# Connectors.net
KiCad netlist of a schematic drawn in Altium Designer
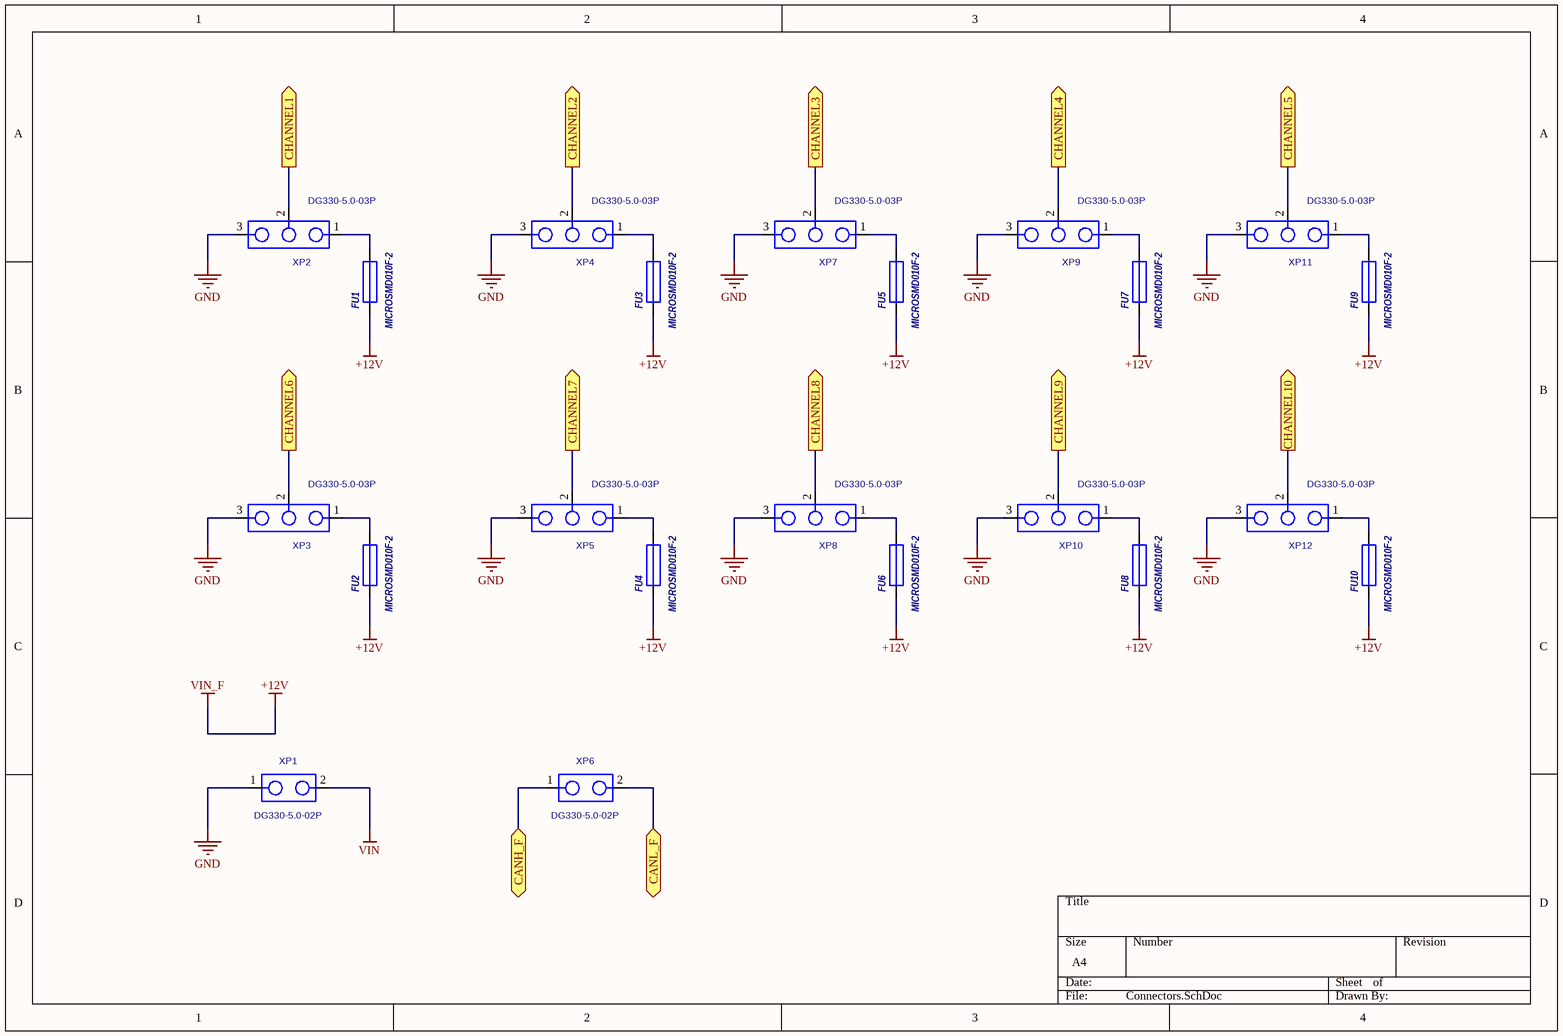
[diagram p0: Connectors.SchDoc]

(export (version "E")
  (design (tool "Eeschema 10.0.6"))
  (components
    (comp (ref "FU1")
      (value "MICROSMD010F-2")
      (footprint "RC1210")
      (description "MICROSMD")
      (libsource (lib "gprs_modem_2") (part "MICROSMD"))
    )
    (comp (ref "FU2")
      (value "MICROSMD010F-2")
      (footprint "RC1210")
      (description "MICROSMD")
      (libsource (lib "gprs_modem_2") (part "MICROSMD"))
    )
    (comp (ref "FU3")
      (value "MICROSMD010F-2")
      (footprint "RC1210")
      (description "MICROSMD")
      (libsource (lib "gprs_modem_2") (part "MICROSMD"))
    )
    (comp (ref "FU4")
      (value "MICROSMD010F-2")
      (footprint "RC1210")
      (description "MICROSMD")
      (libsource (lib "gprs_modem_2") (part "MICROSMD"))
    )
    (comp (ref "FU5")
      (value "MICROSMD010F-2")
      (footprint "RC1210")
      (description "MICROSMD")
      (libsource (lib "gprs_modem_2") (part "MICROSMD"))
    )
    (comp (ref "FU6")
      (value "MICROSMD010F-2")
      (footprint "RC1210")
      (description "MICROSMD")
      (libsource (lib "gprs_modem_2") (part "MICROSMD"))
    )
    (comp (ref "FU7")
      (value "MICROSMD010F-2")
      (footprint "RC1210")
      (description "MICROSMD")
      (libsource (lib "gprs_modem_2") (part "MICROSMD"))
    )
    (comp (ref "FU8")
      (value "MICROSMD010F-2")
      (footprint "RC1210")
      (description "MICROSMD")
      (libsource (lib "gprs_modem_2") (part "MICROSMD"))
    )
    (comp (ref "FU9")
      (value "MICROSMD010F-2")
      (footprint "RC1210")
      (description "MICROSMD")
      (libsource (lib "gprs_modem_2") (part "MICROSMD"))
    )
    (comp (ref "FU10")
      (value "MICROSMD010F-2")
      (footprint "RC1210")
      (description "MICROSMD")
      (libsource (lib "gprs_modem_2") (part "MICROSMD"))
    )
    (comp (ref "XP1")
      (value "DG330-5.0-02P")
      (footprint "330-021")
      (libsource (lib "shlagbaum") (part "DG330-5.0-02P"))
    )
    (comp (ref "XP2")
      (value "DG330-5.0-03P")
      (footprint "DG330-5.0-03P")
      (libsource (lib "shlagbaum") (part "DG330-5.0-03P"))
    )
    (comp (ref "XP3")
      (value "DG330-5.0-03P")
      (footprint "DG330-5.0-03P")
      (libsource (lib "shlagbaum") (part "DG330-5.0-03P"))
    )
    (comp (ref "XP4")
      (value "DG330-5.0-03P")
      (footprint "DG330-5.0-03P")
      (libsource (lib "shlagbaum") (part "DG330-5.0-03P"))
    )
    (comp (ref "XP5")
      (value "DG330-5.0-03P")
      (footprint "DG330-5.0-03P")
      (libsource (lib "shlagbaum") (part "DG330-5.0-03P"))
    )
    (comp (ref "XP6")
      (value "DG330-5.0-02P")
      (footprint "330-021")
      (libsource (lib "shlagbaum") (part "DG330-5.0-02P"))
    )
    (comp (ref "XP7")
      (value "DG330-5.0-03P")
      (footprint "DG330-5.0-03P")
      (libsource (lib "shlagbaum") (part "DG330-5.0-03P"))
    )
    (comp (ref "XP8")
      (value "DG330-5.0-03P")
      (footprint "DG330-5.0-03P")
      (libsource (lib "shlagbaum") (part "DG330-5.0-03P"))
    )
    (comp (ref "XP9")
      (value "DG330-5.0-03P")
      (footprint "DG330-5.0-03P")
      (libsource (lib "shlagbaum") (part "DG330-5.0-03P"))
    )
    (comp (ref "XP10")
      (value "DG330-5.0-03P")
      (footprint "DG330-5.0-03P")
      (libsource (lib "shlagbaum") (part "DG330-5.0-03P"))
    )
    (comp (ref "XP11")
      (value "DG330-5.0-03P")
      (footprint "DG330-5.0-03P")
      (libsource (lib "shlagbaum") (part "DG330-5.0-03P"))
    )
    (comp (ref "XP12")
      (value "DG330-5.0-03P")
      (footprint "DG330-5.0-03P")
      (libsource (lib "shlagbaum") (part "DG330-5.0-03P"))
    )
  )
  (nets
    (net (code "1") (name "+12V") (class "Default")
      (node (ref "FU1") (pin "1") (pintype "passive"))
      (node (ref "FU10") (pin "1") (pintype "passive"))
      (node (ref "FU2") (pin "1") (pintype "passive"))
      (node (ref "FU3") (pin "1") (pintype "passive"))
      (node (ref "FU4") (pin "1") (pintype "passive"))
      (node (ref "FU5") (pin "1") (pintype "passive"))
      (node (ref "FU6") (pin "1") (pintype "passive"))
      (node (ref "FU7") (pin "1") (pintype "passive"))
      (node (ref "FU8") (pin "1") (pintype "passive"))
      (node (ref "FU9") (pin "1") (pintype "passive"))
    )
    (net (code "2") (name "/CANH_F") (class "Default") (node (ref "XP6") (pin "1") (pintype "passive")))
    (net (code "3") (name "/CANL_F") (class "Default") (node (ref "XP6") (pin "2") (pintype "passive")))
    (net (code "4") (name "/CHANNEL1") (class "Default") (node (ref "XP2") (pin "2") (pintype "passive")))
    (net (code "5") (name "/CHANNEL2") (class "Default") (node (ref "XP4") (pin "2") (pintype "passive")))
    (net (code "6") (name "/CHANNEL3") (class "Default") (node (ref "XP7") (pin "2") (pintype "passive")))
    (net (code "7") (name "/CHANNEL4") (class "Default") (node (ref "XP9") (pin "2") (pintype "passive")))
    (net (code "8") (name "/CHANNEL5") (class "Default") (node (ref "XP11") (pin "2") (pintype "passive")))
    (net (code "9") (name "/CHANNEL6") (class "Default") (node (ref "XP3") (pin "2") (pintype "passive")))
    (net (code "10") (name "/CHANNEL7") (class "Default") (node (ref "XP5") (pin "2") (pintype "passive")))
    (net (code "11") (name "/CHANNEL8") (class "Default") (node (ref "XP8") (pin "2") (pintype "passive")))
    (net (code "12") (name "/CHANNEL9") (class "Default") (node (ref "XP10") (pin "2") (pintype "passive")))
    (net (code "13") (name "/CHANNEL10") (class "Default") (node (ref "XP12") (pin "2") (pintype "passive")))
    (net (code "14") (name "GND") (class "Default")
      (node (ref "XP1") (pin "1") (pintype "passive"))
      (node (ref "XP10") (pin "3") (pintype "passive"))
      (node (ref "XP11") (pin "3") (pintype "passive"))
      (node (ref "XP12") (pin "3") (pintype "passive"))
      (node (ref "XP2") (pin "3") (pintype "passive"))
      (node (ref "XP3") (pin "3") (pintype "passive"))
      (node (ref "XP4") (pin "3") (pintype "passive"))
      (node (ref "XP5") (pin "3") (pintype "passive"))
      (node (ref "XP7") (pin "3") (pintype "passive"))
      (node (ref "XP8") (pin "3") (pintype "passive"))
      (node (ref "XP9") (pin "3") (pintype "passive"))
    )
    (net (code "15") (name "Net-(FU1-Pad2)") (class "Default")
      (node (ref "FU1") (pin "2") (pintype "passive"))
      (node (ref "XP2") (pin "1") (pintype "passive"))
    )
    (net (code "16") (name "Net-(FU2-Pad2)") (class "Default")
      (node (ref "FU2") (pin "2") (pintype "passive"))
      (node (ref "XP3") (pin "1") (pintype "passive"))
    )
    (net (code "17") (name "Net-(FU3-Pad2)") (class "Default")
      (node (ref "FU3") (pin "2") (pintype "passive"))
      (node (ref "XP4") (pin "1") (pintype "passive"))
    )
    (net (code "18") (name "Net-(FU4-Pad2)") (class "Default")
      (node (ref "FU4") (pin "2") (pintype "passive"))
      (node (ref "XP5") (pin "1") (pintype "passive"))
    )
    (net (code "19") (name "Net-(FU5-Pad2)") (class "Default")
      (node (ref "FU5") (pin "2") (pintype "passive"))
      (node (ref "XP7") (pin "1") (pintype "passive"))
    )
    (net (code "20") (name "Net-(FU6-Pad2)") (class "Default")
      (node (ref "FU6") (pin "2") (pintype "passive"))
      (node (ref "XP8") (pin "1") (pintype "passive"))
    )
    (net (code "21") (name "Net-(FU7-Pad2)") (class "Default")
      (node (ref "FU7") (pin "2") (pintype "passive"))
      (node (ref "XP9") (pin "1") (pintype "passive"))
    )
    (net (code "22") (name "Net-(FU8-Pad2)") (class "Default")
      (node (ref "FU8") (pin "2") (pintype "passive"))
      (node (ref "XP10") (pin "1") (pintype "passive"))
    )
    (net (code "23") (name "Net-(FU9-Pad2)") (class "Default")
      (node (ref "FU9") (pin "2") (pintype "passive"))
      (node (ref "XP11") (pin "1") (pintype "passive"))
    )
    (net (code "24") (name "Net-(FU10-Pad2)") (class "Default")
      (node (ref "FU10") (pin "2") (pintype "passive"))
      (node (ref "XP12") (pin "1") (pintype "passive"))
    )
    (net (code "25") (name "VIN") (class "Default") (node (ref "XP1") (pin "2") (pintype "passive")))
  )
)
